# M24512-DFMC6TG.net
KiCad netlist of a schematic drawn in Altium Designer
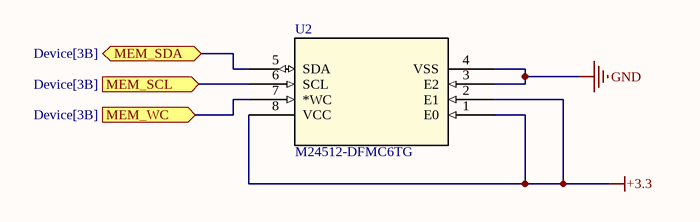
[diagram p0: M24512-DFMC6TG.SchDoc]

(export (version "E")
  (design (tool "Eeschema 10.0.6"))
  (components
    (comp (ref "U2")
      (value "M24512-DFMC6TG")
      (footprint "UFDFPN8_STM")
      (fields (field (name "COPYRIGHT") "Copyright (C) 2023 Ultra Librarian. All rights reserved."))
      (libsource (lib "ANT") (part "M24512-DFMC6TG"))
    )
  )
  (nets
    (net (code "1") (name "+3.3") (class "Default")
      (node (ref "U2") (pin "1") (pinfunction "E0_1") (pintype "input"))
      (node (ref "U2") (pin "2") (pinfunction "E1_2") (pintype "input"))
      (node (ref "U2") (pin "8") (pinfunction "VCC_8") (pintype "power_in"))
    )
    (net (code "2") (name "/MEM_SCL") (class "Default")
      (node (ref "U2") (pin "6") (pinfunction "SCL_6") (pintype "input"))
    )
    (net (code "3") (name "/MEM_SDA") (class "Default")
      (node (ref "U2") (pin "5") (pinfunction "SDA_5") (pintype "bidirectional"))
    )
    (net (code "4") (name "/MEM_WC") (class "Default")
      (node (ref "U2") (pin "7") (pinfunction "*WC_7") (pintype "input"))
    )
    (net (code "5") (name "GND") (class "Default")
      (node (ref "U2") (pin "3") (pinfunction "E2_3") (pintype "input"))
      (node (ref "U2") (pin "4") (pinfunction "VSS_4") (pintype "passive"))
    )
  )
)
